# PowerManagement.net
KiCad netlist of a schematic drawn in Altium Designer
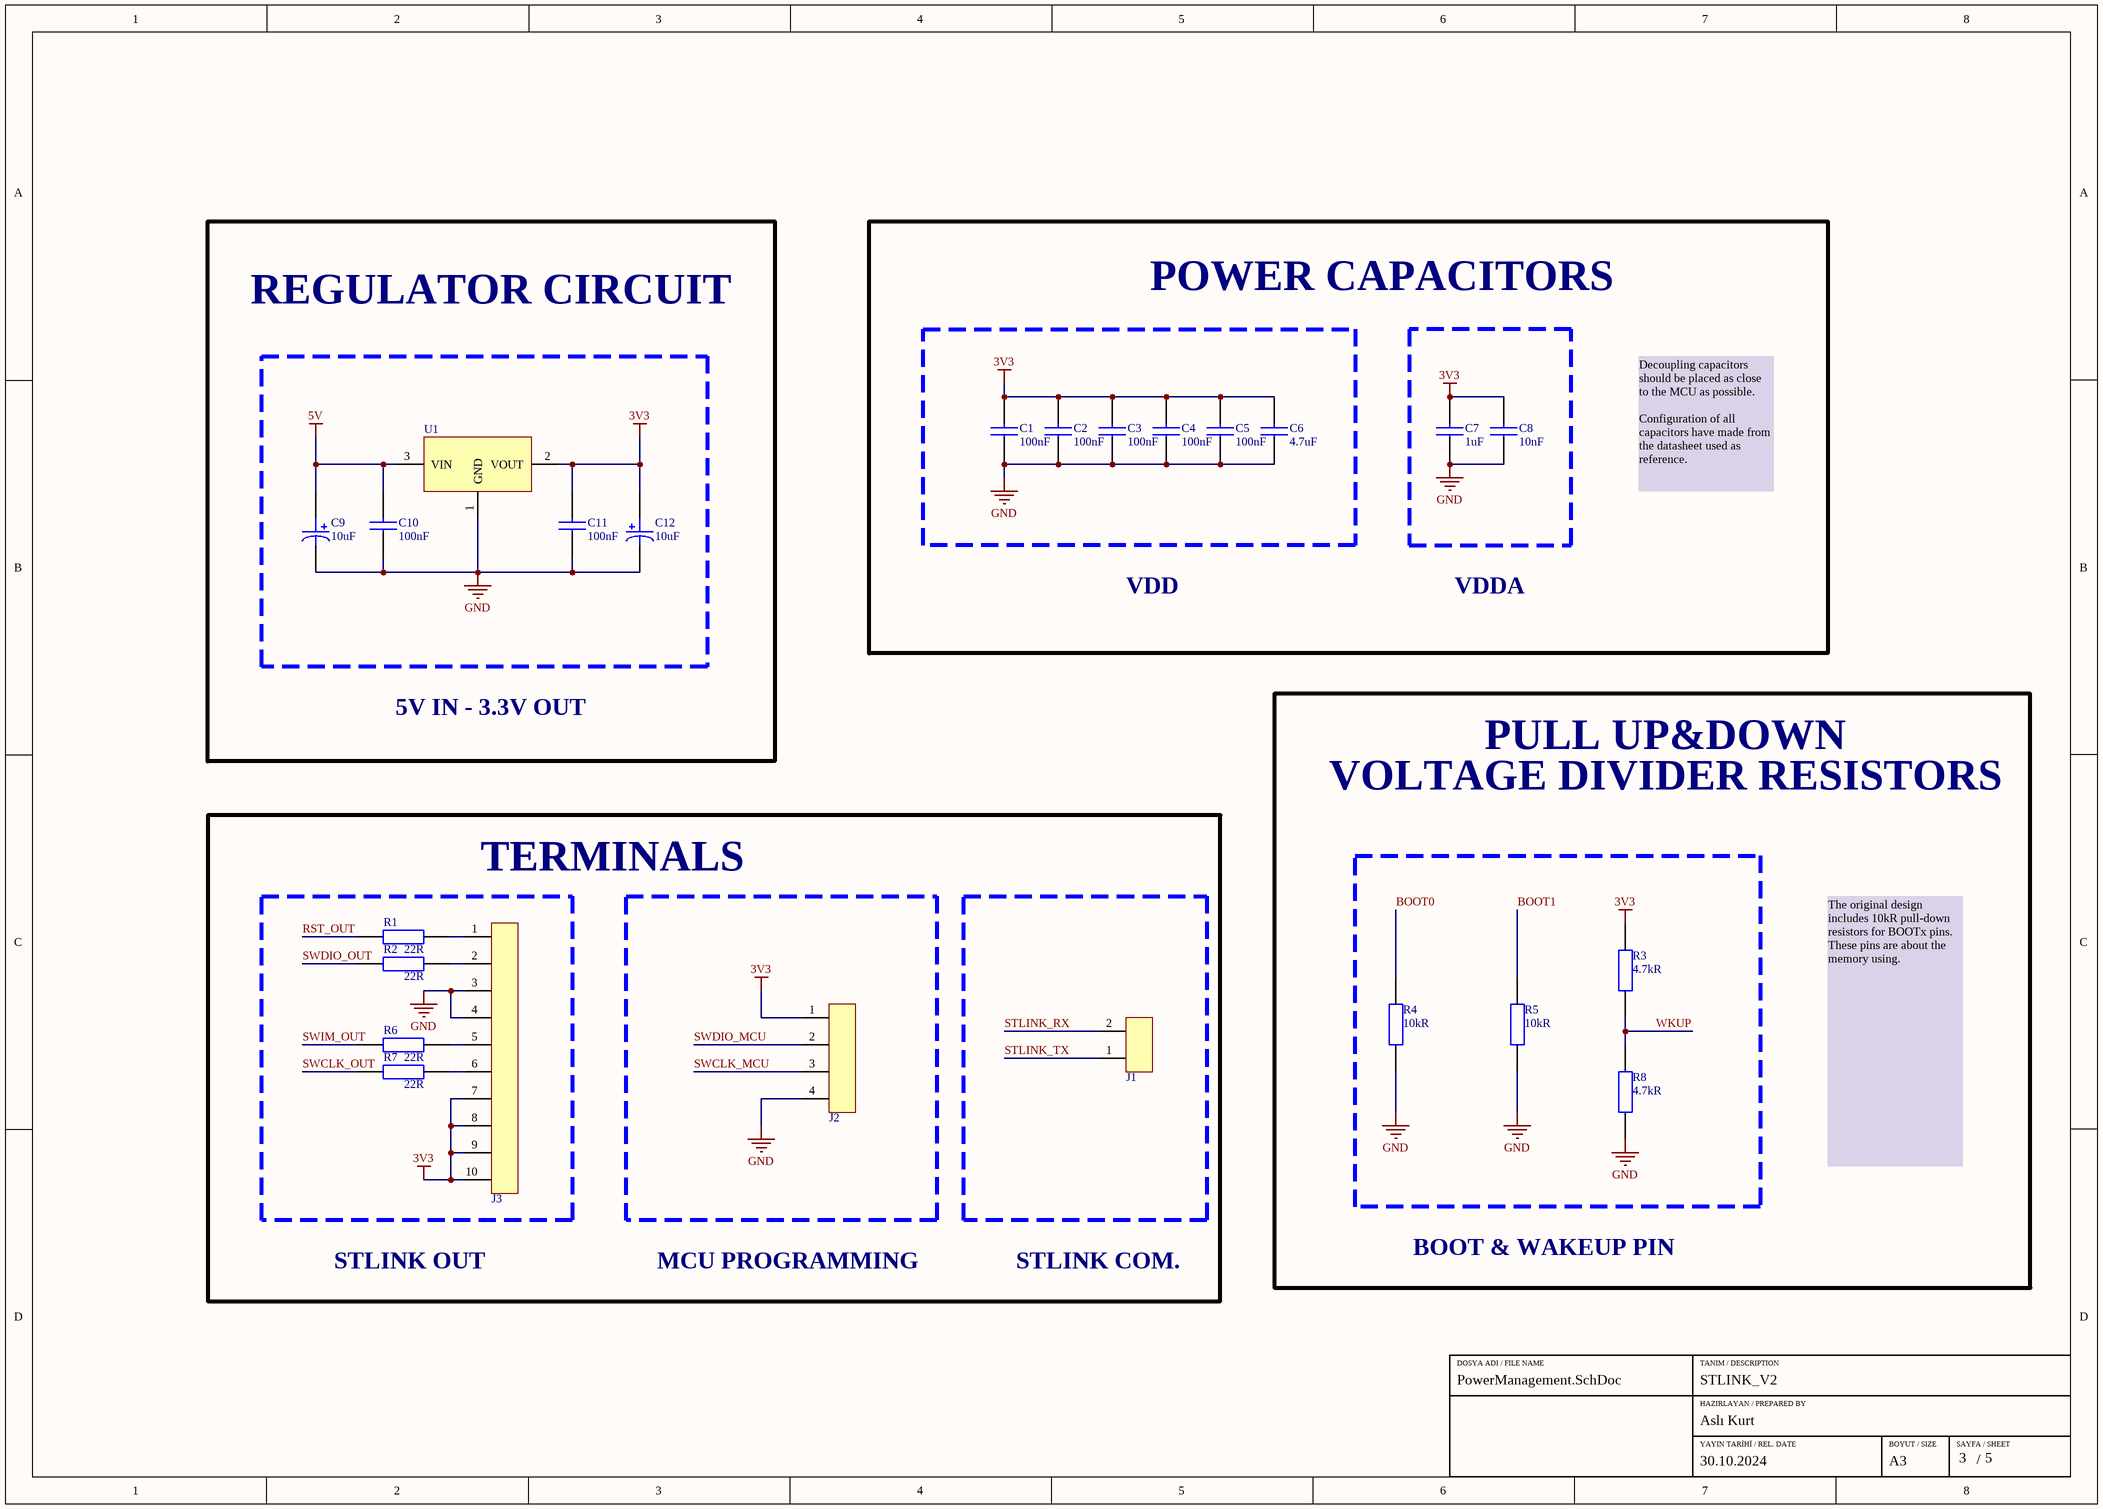
[diagram p0: PowerManagement.SchDoc]

(export (version "E")
  (design (tool "Eeschema 10.0.6"))
  (components
    (comp (ref "C1")
      (value "C0603C104K5RACTU")
      (footprint "CAP_0603")
      (description "CAP CER 100nF %10 0603 SMD")
      (fields
        (field (name "MANUFACTURER") "KEMET")
        (field (name "TOLERANCE") "10%")
        (field (name "CAPACITANCE") "100nF")
        (field (name "DESIGNEDBY") "Aslı Kurt")
      )
      (libsource (lib "MyLibrary") (part "CAP CER 100nF 0603"))
    )
    (comp (ref "C2")
      (value "C0603C104K5RACTU")
      (footprint "CAP_0603")
      (description "CAP CER 100nF %10 0603 SMD")
      (fields
        (field (name "MANUFACTURER") "KEMET")
        (field (name "TOLERANCE") "10%")
        (field (name "CAPACITANCE") "100nF")
        (field (name "DESIGNEDBY") "Aslı Kurt")
      )
      (libsource (lib "MyLibrary") (part "CAP CER 100nF 0603"))
    )
    (comp (ref "C3")
      (value "C0603C104K5RACTU")
      (footprint "CAP_0603")
      (description "CAP CER 100nF %10 0603 SMD")
      (fields
        (field (name "MANUFACTURER") "KEMET")
        (field (name "TOLERANCE") "10%")
        (field (name "CAPACITANCE") "100nF")
        (field (name "DESIGNEDBY") "Aslı Kurt")
      )
      (libsource (lib "MyLibrary") (part "CAP CER 100nF 0603"))
    )
    (comp (ref "C4")
      (value "C0603C104K5RACTU")
      (footprint "CAP_0603")
      (description "CAP CER 100nF %10 0603 SMD")
      (fields
        (field (name "MANUFACTURER") "KEMET")
        (field (name "TOLERANCE") "10%")
        (field (name "CAPACITANCE") "100nF")
        (field (name "DESIGNEDBY") "Aslı Kurt")
      )
      (libsource (lib "MyLibrary") (part "CAP CER 100nF 0603"))
    )
    (comp (ref "C5")
      (value "C0603C104K5RACTU")
      (footprint "CAP_0603")
      (description "CAP CER 100nF %10 0603 SMD")
      (fields
        (field (name "MANUFACTURER") "KEMET")
        (field (name "TOLERANCE") "10%")
        (field (name "CAPACITANCE") "100nF")
        (field (name "DESIGNEDBY") "Aslı Kurt")
      )
      (libsource (lib "MyLibrary") (part "CAP CER 100nF 0603"))
    )
    (comp (ref "C6")
      (value "CL21A475KAQNNNE")
      (footprint "CAP_0805")
      (description "CAP CER 4.7uF %10 0805")
      (fields
        (field (name "MANUFACTURER") "Samsung")
        (field (name "TOLERANCE") "10%")
        (field (name "CAPACITANCE") "4.7uF")
        (field (name "DESIGNEDBY") "Aslı Kurt")
      )
      (libsource (lib "MyLibrary") (part "CAP CER 4.7uF 0805"))
    )
    (comp (ref "C7")
      (value "CL21B105KBFNNNE")
      (footprint "CAP_0805")
      (description "CAP CER 1uF %10 0805")
      (fields
        (field (name "MANUFACTURER") "Samsung")
        (field (name "TOLERANCE") "10%")
        (field (name "CAPACITANCE") "1uF")
        (field (name "DESIGNEDBY") "Aslı Kurt")
      )
      (libsource (lib "MyLibrary") (part "CAP CER 1uF 0805"))
    )
    (comp (ref "C8")
      (value "0603B103K160CT")
      (footprint "CAP_0603")
      (description "CAP CER 10nF %10 0603")
      (fields
        (field (name "MANUFACTURER") "Walsin Technologies")
        (field (name "TOLERANCE") "10%")
        (field (name "CAPACITANCE") "10nF")
        (field (name "DESIGNEDBY") "Aslı Kurt")
      )
      (libsource (lib "MyLibrary") (part "CAP CER 10nF 0603"))
    )
    (comp (ref "C9")
      (value "T491A106K010AT")
      (footprint "CAP_1206_TANT")
      (description "Cap Tant Solid 10uF 10V A CASE 10% (3.2 X 1.6 X 1.6mm) SMD 3216-18 4 Ohm 125 C T/R")
      (fields
        (field (name "MANUFACTURER") "KEMET")
        (field (name "TOLERANCE") "10%")
        (field (name "CAPACITANCE") "10uF")
        (field (name "DESIGNEDBY") "Aslı Kurt")
      )
      (libsource (lib "") (part "CAP TANT 10uF 1206_1"))
    )
    (comp (ref "C10")
      (value "C0603C104K5RACTU")
      (footprint "CAP_0603")
      (description "CAP CER 100nF %10 0603 SMD")
      (fields
        (field (name "MANUFACTURER") "KEMET")
        (field (name "TOLERANCE") "10%")
        (field (name "CAPACITANCE") "100nF")
        (field (name "DESIGNEDBY") "Aslı Kurt")
      )
      (libsource (lib "MyLibrary") (part "CAP CER 100nF 0603"))
    )
    (comp (ref "C11")
      (value "C0603C104K5RACTU")
      (footprint "CAP_0603")
      (description "CAP CER 100nF %10 0603 SMD")
      (fields
        (field (name "MANUFACTURER") "KEMET")
        (field (name "TOLERANCE") "10%")
        (field (name "CAPACITANCE") "100nF")
        (field (name "DESIGNEDBY") "Aslı Kurt")
      )
      (libsource (lib "MyLibrary") (part "CAP CER 100nF 0603"))
    )
    (comp (ref "C12")
      (value "T491A106K010AT")
      (footprint "CAP_1206_TANT")
      (description "Cap Tant Solid 10uF 10V A CASE 10% (3.2 X 1.6 X 1.6mm) SMD 3216-18 4 Ohm 125 C T/R")
      (fields
        (field (name "MANUFACTURER") "KEMET")
        (field (name "TOLERANCE") "10%")
        (field (name "CAPACITANCE") "10uF")
        (field (name "DESIGNEDBY") "Aslı Kurt")
      )
      (libsource (lib "MyLibrary") (part "CAP TANT 10uF 1206"))
    )
    (comp (ref "J1")
      (value "61300211121")
      (footprint "2x1 Male Header 2.54mm")
      (fields (field (name "DESIGNEDBY") "Aslı Kurt"))
      (libsource (lib "MyLibrary") (part "2x1 Male Header 2.54mm"))
    )
    (comp (ref "J2")
      (value "2.54mm")
      (footprint "4x1 Pinout")
      (libsource (lib "MyLibrary") (part "4x1 Pinout"))
    )
    (comp (ref "J3")
      (value "SBH11-PBPC-D05-RA-BK")
      (footprint "5x2 Male Header 2.54mm Shrouded - 4 Wall")
      (description "Conn Shrouded Header (4 Sides) HDR 10 POS 2.54mm Solder RA Side Entry Thru-Hole")
      (fields (field (name "MANUFACTURER") "Sullins") (field (name "DESIGNEDBY") "Aslı Kurt"))
      (libsource (lib "MyLibrary") (part "5x2 Male Header 2.54mm Shrouded - 4 Wall"))
    )
    (comp (ref "R1")
      (value "AC0201FR-0722RL")
      (footprint "RES_0201")
      (description "SMD Chip Resistor, 22 Ohm, ± 1%, 50 mW, 0201 [0603 Metric], Thick Film, General Purpose")
      (fields
        (field (name "MANUFACTURER") "Yageo")
        (field (name "RESISTANCE") "22R")
        (field (name "DESIGNEDBY") "Aslı Kurt")
      )
      (libsource (lib "MyLibrary") (part "RES 22 OHM 0201"))
    )
    (comp (ref "R2")
      (value "AC0201FR-0722RL")
      (footprint "RES_0201")
      (description "SMD Chip Resistor, 22 Ohm, ± 1%, 50 mW, 0201 [0603 Metric], Thick Film, General Purpose")
      (fields
        (field (name "MANUFACTURER") "Yageo")
        (field (name "RESISTANCE") "22R")
        (field (name "DESIGNEDBY") "Aslı Kurt")
      )
      (libsource (lib "MyLibrary") (part "RES 22 OHM 0201"))
    )
    (comp (ref "R3")
      (value "RC0603JR-074K7L")
      (footprint "RES_0603")
      (description "RES 4K7 %5 OHM 0603 SMD")
      (fields
        (field (name "MANUFACTURER") "Yageo")
        (field (name "TOLERANCE") "5%")
        (field (name "RESISTANCE") "4.7kR")
        (field (name "DESIGNEDBY") "Aslı Kurt")
      )
      (libsource (lib "MyLibrary") (part "RES 4K7 OHM 0603"))
    )
    (comp (ref "R4")
      (value "RC0603FR-0710KL")
      (footprint "RES_0603")
      (description "RES 10K %1 OHM 0603 SMD")
      (fields
        (field (name "MANUFACTURER") "Yageo")
        (field (name "TOLERANCE") "1%")
        (field (name "RESISTANCE") "10kR")
        (field (name "DESIGNEDBY") "Aslı Kurt")
      )
      (libsource (lib "MyLibrary") (part "RES 10K OHM 0603"))
    )
    (comp (ref "R5")
      (value "RC0603FR-0710KL")
      (footprint "RES_0603")
      (description "RES 10K %1 OHM 0603 SMD")
      (fields
        (field (name "MANUFACTURER") "Yageo")
        (field (name "TOLERANCE") "1%")
        (field (name "RESISTANCE") "10kR")
        (field (name "DESIGNEDBY") "Aslı Kurt")
      )
      (libsource (lib "MyLibrary") (part "RES 10K OHM 0603"))
    )
    (comp (ref "R6")
      (value "AC0201FR-0722RL")
      (footprint "RES_0201")
      (description "SMD Chip Resistor, 22 Ohm, ± 1%, 50 mW, 0201 [0603 Metric], Thick Film, General Purpose")
      (fields
        (field (name "MANUFACTURER") "Yageo")
        (field (name "RESISTANCE") "22R")
        (field (name "DESIGNEDBY") "Aslı Kurt")
      )
      (libsource (lib "MyLibrary") (part "RES 22 OHM 0201"))
    )
    (comp (ref "R7")
      (value "AC0201FR-0722RL")
      (footprint "RES_0201")
      (description "SMD Chip Resistor, 22 Ohm, ± 1%, 50 mW, 0201 [0603 Metric], Thick Film, General Purpose")
      (fields
        (field (name "MANUFACTURER") "Yageo")
        (field (name "RESISTANCE") "22R")
        (field (name "DESIGNEDBY") "Aslı Kurt")
      )
      (libsource (lib "MyLibrary") (part "RES 22 OHM 0201"))
    )
    (comp (ref "R8")
      (value "RC0603JR-074K7L")
      (footprint "RES_0603")
      (description "RES 4K7 %5 OHM 0603 SMD")
      (fields
        (field (name "MANUFACTURER") "Yageo")
        (field (name "TOLERANCE") "5%")
        (field (name "RESISTANCE") "4.7kR")
        (field (name "DESIGNEDBY") "Aslı Kurt")
      )
      (libsource (lib "MyLibrary") (part "RES 4K7 OHM 0603"))
    )
    (comp (ref "U1")
      (value "LM1117MPX-33NOPB")
      (footprint "SOT223")
      (description "800-mA 15-V linear voltage regulator ; 4-SOT-223 0 to 125")
      (fields
        (field (name "MANUFACTURER") "Texas Instruments")
        (field (name "MANUFACTURER PART NUMBER") "LM1117MPX-3.3/NOPB")
        (field (name "DESIGNEDBY") "Aslı Kurt")
      )
      (libsource (lib "MyLibrary") (part "LM1117MPX-33NOPB"))
    )
  )
  (nets
    (net (code "1") (name "/BOOT0") (class "Default")
      (node (ref "R4") (pin "1") (pinfunction "1_1") (pintype "passive"))
    )
    (net (code "2") (name "/BOOT1") (class "Default")
      (node (ref "R5") (pin "1") (pinfunction "1_1") (pintype "passive"))
    )
    (net (code "3") (name "/RST_OUT") (class "Default")
      (node (ref "R1") (pin "1") (pinfunction "1_1") (pintype "passive"))
    )
    (net (code "4") (name "/STLINK_RX") (class "Default")
      (node (ref "J1") (pin "2") (pinfunction "2_2") (pintype "power_in"))
    )
    (net (code "5") (name "/STLINK_TX") (class "Default")
      (node (ref "J1") (pin "1") (pinfunction "1_1") (pintype "power_in"))
    )
    (net (code "6") (name "/SWCLK_MCU") (class "Default")
      (node (ref "J2") (pin "3") (pinfunction "3_3") (pintype "power_in"))
    )
    (net (code "7") (name "/SWCLK_OUT") (class "Default")
      (node (ref "R7") (pin "1") (pinfunction "1_1") (pintype "passive"))
    )
    (net (code "8") (name "/SWDIO_MCU") (class "Default")
      (node (ref "J2") (pin "2") (pinfunction "2_2") (pintype "power_in"))
    )
    (net (code "9") (name "/SWDIO_OUT") (class "Default")
      (node (ref "R2") (pin "1") (pinfunction "1_1") (pintype "passive"))
    )
    (net (code "10") (name "/SWIM_OUT") (class "Default")
      (node (ref "R6") (pin "1") (pinfunction "1_1") (pintype "passive"))
    )
    (net (code "11") (name "/WKUP") (class "Default")
      (node (ref "R3") (pin "1") (pinfunction "1_1") (pintype "passive"))
      (node (ref "R8") (pin "2") (pinfunction "2_2") (pintype "passive"))
    )
    (net (code "12") (name "3V3") (class "Default")
      (node (ref "C1") (pin "2") (pinfunction "2_2") (pintype "passive"))
      (node (ref "C11") (pin "2") (pinfunction "2_2") (pintype "passive"))
      (node (ref "C12") (pin "1") (pinfunction "1_1") (pintype "passive"))
      (node (ref "C2") (pin "2") (pinfunction "2_2") (pintype "passive"))
      (node (ref "C3") (pin "2") (pinfunction "2_2") (pintype "passive"))
      (node (ref "C4") (pin "2") (pinfunction "2_2") (pintype "passive"))
      (node (ref "C5") (pin "2") (pinfunction "2_2") (pintype "passive"))
      (node (ref "C6") (pin "2") (pinfunction "2_2") (pintype "passive"))
      (node (ref "C7") (pin "2") (pinfunction "2_2") (pintype "passive"))
      (node (ref "C8") (pin "2") (pinfunction "2_2") (pintype "passive"))
      (node (ref "J2") (pin "1") (pinfunction "1_1") (pintype "power_in"))
      (node (ref "J3") (pin "10") (pinfunction "10_10") (pintype "passive"))
      (node (ref "J3") (pin "7") (pinfunction "7_7") (pintype "passive"))
      (node (ref "J3") (pin "8") (pinfunction "8_8") (pintype "passive"))
      (node (ref "J3") (pin "9") (pinfunction "9_9") (pintype "passive"))
      (node (ref "R3") (pin "2") (pinfunction "2_2") (pintype "passive"))
      (node (ref "U1") (pin "2") (pinfunction "VOUT_2") (pintype "passive"))
    )
    (net (code "13") (name "5V") (class "Default")
      (node (ref "C10") (pin "2") (pinfunction "2_2") (pintype "passive"))
      (node (ref "C9") (pin "1") (pinfunction "1_1") (pintype "passive"))
      (node (ref "U1") (pin "3") (pinfunction "VIN_3") (pintype "passive"))
    )
    (net (code "14") (name "GND") (class "Default")
      (node (ref "C1") (pin "1") (pinfunction "1_1") (pintype "passive"))
      (node (ref "C10") (pin "1") (pinfunction "1_1") (pintype "passive"))
      (node (ref "C11") (pin "1") (pinfunction "1_1") (pintype "passive"))
      (node (ref "C12") (pin "2") (pinfunction "2_2") (pintype "passive"))
      (node (ref "C2") (pin "1") (pinfunction "1_1") (pintype "passive"))
      (node (ref "C3") (pin "1") (pinfunction "1_1") (pintype "passive"))
      (node (ref "C4") (pin "1") (pinfunction "1_1") (pintype "passive"))
      (node (ref "C5") (pin "1") (pinfunction "1_1") (pintype "passive"))
      (node (ref "C6") (pin "1") (pinfunction "1_1") (pintype "passive"))
      (node (ref "C7") (pin "1") (pinfunction "1_1") (pintype "passive"))
      (node (ref "C8") (pin "1") (pinfunction "1_1") (pintype "passive"))
      (node (ref "C9") (pin "2") (pinfunction "2_2") (pintype "passive"))
      (node (ref "J2") (pin "4") (pinfunction "4_4") (pintype "power_in"))
      (node (ref "J3") (pin "3") (pinfunction "3_3") (pintype "power_in"))
      (node (ref "J3") (pin "4") (pinfunction "4_4") (pintype "power_in"))
      (node (ref "R4") (pin "2") (pinfunction "2_2") (pintype "passive"))
      (node (ref "R5") (pin "2") (pinfunction "2_2") (pintype "passive"))
      (node (ref "R8") (pin "1") (pinfunction "1_1") (pintype "passive"))
      (node (ref "U1") (pin "1") (pinfunction "GND_1") (pintype "passive"))
    )
    (net (code "15") (name "Net-(J3-Pad1)") (class "Default")
      (node (ref "J3") (pin "1") (pinfunction "1_1") (pintype "power_in"))
      (node (ref "R1") (pin "2") (pinfunction "2_2") (pintype "passive"))
    )
    (net (code "16") (name "Net-(J3-Pad2)") (class "Default")
      (node (ref "J3") (pin "2") (pinfunction "2_2") (pintype "power_in"))
      (node (ref "R2") (pin "2") (pinfunction "2_2") (pintype "passive"))
    )
    (net (code "17") (name "Net-(J3-Pad5)") (class "Default")
      (node (ref "J3") (pin "5") (pinfunction "5_5") (pintype "passive"))
      (node (ref "R6") (pin "2") (pinfunction "2_2") (pintype "passive"))
    )
    (net (code "18") (name "Net-(J3-Pad6)") (class "Default")
      (node (ref "J3") (pin "6") (pinfunction "6_6") (pintype "passive"))
      (node (ref "R7") (pin "2") (pinfunction "2_2") (pintype "passive"))
    )
  )
)
